# Sheet4.net
KiCad netlist of a schematic drawn in Altium Designer
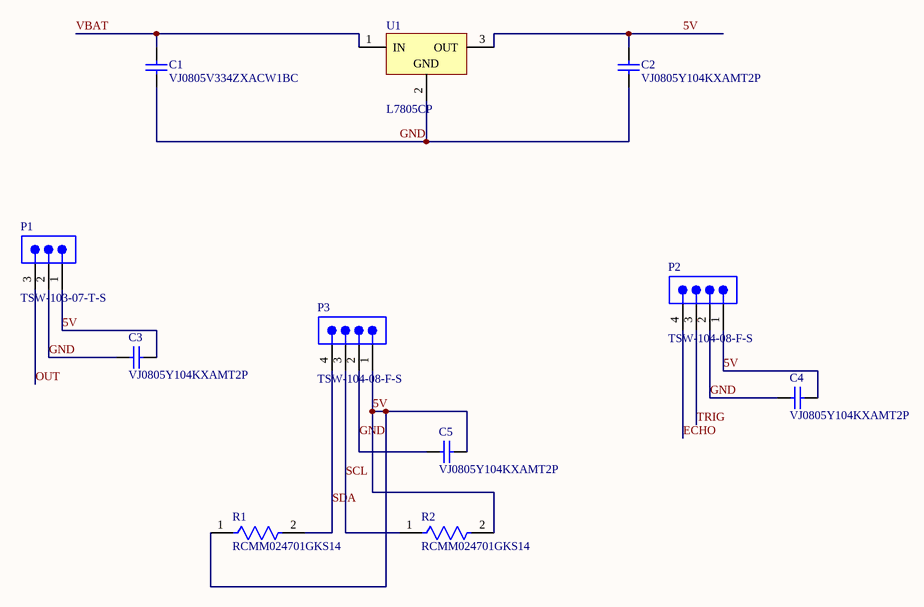
[diagram p0: Sheet4.SchDoc]

(export (version "E")
  (design (tool "Eeschema 10.0.6"))
  (components
    (comp (ref "C1")
      (value "VJ0805V334ZXACW1BC")
      (footprint "CAPC2013X145X50NL20T20")
      (fields (field (name "MANUFACTURER") "Vitramon"))
      (libsource (lib "Altium Content Vault") (part "CAP"))
    )
    (comp (ref "C2")
      (value "VJ0805Y104KXAMT2P")
      (footprint "CAPC2013X145X48LL20T23")
      (fields (field (name "MANUFACTURER") "Vishay"))
      (libsource (lib "Altium Content Vault") (part "CAP"))
    )
    (comp (ref "C3")
      (value "VJ0805Y104KXAMT2P")
      (footprint "CAPC2013X145X48LL20T23")
      (fields (field (name "MANUFACTURER") "Vishay"))
      (libsource (lib "Altium Content Vault") (part "CAP"))
    )
    (comp (ref "C4")
      (value "VJ0805Y104KXAMT2P")
      (footprint "CAPC2013X145X48LL20T23")
      (fields (field (name "MANUFACTURER") "Vishay"))
      (libsource (lib "Altium Content Vault") (part "CAP"))
    )
    (comp (ref "C5")
      (value "VJ0805Y104KXAMT2P")
      (footprint "CAPC2013X145X48LL20T23")
      (fields (field (name "MANUFACTURER") "Vishay"))
      (libsource (lib "Altium Content Vault") (part "CAP"))
    )
    (comp (ref "P1")
      (value "TSW-103-07-T-S")
      (footprint "SMTC-TSW-103-07-X-S")
      (description "0.025\" SQ Post Header, Through-hole, Vertical, -55 to 105 degC, 2.54 mm Pitch, 3-Pin, Male, RoHS")
      (fields (field (name "MANUFACTURER") "Samtec"))
      (libsource (lib "Altium Content Vault") (part "SMTC-TSW-103-X-X-S-X"))
    )
    (comp (ref "P2")
      (value "TSW-104-08-F-S")
      (footprint "SMTC-TSW-104-08-X-S")
      (description "0.025\" SQ Post Header, Through-hole, Vertical, -55 to 125 degC, 2.54 mm Pitch, 4-Pin, Male, RoHS")
      (fields (field (name "MANUFACTURER") "Samtec"))
      (libsource (lib "Altium Content Vault") (part "SMTC-TSW-104-08-X-S"))
    )
    (comp (ref "P3")
      (value "TSW-104-08-F-S")
      (footprint "SMTC-TSW-104-08-X-S")
      (description "0.025\" SQ Post Header, Through-hole, Vertical, -55 to 125 degC, 2.54 mm Pitch, 4-Pin, Male, RoHS")
      (fields (field (name "MANUFACTURER") "Samtec"))
      (libsource (lib "Altium Content Vault") (part "SMTC-TSW-104-08-X-S"))
    )
    (comp (ref "R1")
      (value "RCMM024701GKS14")
      (footprint "FP-RCMM02-MFG")
      (description "RES 4.7K OHM 2% 1/2W AXIAL")
      (fields (field (name "TOLERANCE") "2%"))
      (libsource (lib "Altium Content Vault") (part "1029c3af85768c4190bb7ad29bc67b5"))
    )
    (comp (ref "R2")
      (value "RCMM024701GKS14")
      (footprint "FP-RCMM02-MFG")
      (description "RES 4.7K OHM 2% 1/2W AXIAL")
      (fields (field (name "TOLERANCE") "2%"))
      (libsource (lib "Altium Content Vault") (part "1029c3af85768c4190bb7ad29bc67b5"))
    )
    (comp (ref "U1")
      (value "L7805CP")
      (footprint "TO220FP")
      (description "Positive Voltage Regulator, 5V, 3-Pin TO-220FP")
      (libsource (lib "Altium Content Vault") (part "PM-REG-L4940-SIL3"))
    )
  )
  (nets
    (net (code "1") (name "/5V") (class "Default")
      (node (ref "C2") (pin "2") (pinfunction "2_2") (pintype "passive"))
      (node (ref "C3") (pin "2") (pinfunction "2_2") (pintype "passive"))
      (node (ref "C4") (pin "2") (pinfunction "2_2") (pintype "passive"))
      (node (ref "C5") (pin "2") (pinfunction "2_2") (pintype "passive"))
      (node (ref "P1") (pin "1") (pinfunction "1_1") (pintype "passive"))
      (node (ref "P2") (pin "1") (pinfunction "1_1") (pintype "passive"))
      (node (ref "P3") (pin "1") (pinfunction "1_1") (pintype "passive"))
      (node (ref "R1") (pin "1") (pinfunction "1_1") (pintype "passive"))
      (node (ref "R2") (pin "2") (pinfunction "2_2") (pintype "passive"))
      (node (ref "U1") (pin "3") (pinfunction "OUT_3") (pintype "power_in"))
    )
    (net (code "2") (name "/ECHO") (class "Default")
      (node (ref "P2") (pin "4") (pinfunction "4_4") (pintype "passive"))
    )
    (net (code "3") (name "/GND") (class "Default")
      (node (ref "C1") (pin "1") (pinfunction "1_1") (pintype "passive"))
      (node (ref "C2") (pin "1") (pinfunction "1_1") (pintype "passive"))
      (node (ref "C3") (pin "1") (pinfunction "1_1") (pintype "passive"))
      (node (ref "C4") (pin "1") (pinfunction "1_1") (pintype "passive"))
      (node (ref "C5") (pin "1") (pinfunction "1_1") (pintype "passive"))
      (node (ref "P1") (pin "2") (pinfunction "2_2") (pintype "passive"))
      (node (ref "P2") (pin "2") (pinfunction "2_2") (pintype "passive"))
      (node (ref "P3") (pin "2") (pinfunction "2_2") (pintype "passive"))
      (node (ref "U1") (pin "2") (pinfunction "GND_2") (pintype "power_in"))
    )
    (net (code "4") (name "/OUT") (class "Default")
      (node (ref "P1") (pin "3") (pinfunction "3_3") (pintype "passive"))
    )
    (net (code "5") (name "/SCL") (class "Default")
      (node (ref "P3") (pin "3") (pinfunction "3_3") (pintype "passive"))
      (node (ref "R2") (pin "1") (pinfunction "1_1") (pintype "passive"))
    )
    (net (code "6") (name "/SDA") (class "Default")
      (node (ref "P3") (pin "4") (pinfunction "4_4") (pintype "passive"))
      (node (ref "R1") (pin "2") (pinfunction "2_2") (pintype "passive"))
    )
    (net (code "7") (name "/TRIG") (class "Default")
      (node (ref "P2") (pin "3") (pinfunction "3_3") (pintype "passive"))
    )
    (net (code "8") (name "/VBAT") (class "Default")
      (node (ref "C1") (pin "2") (pinfunction "2_2") (pintype "passive"))
      (node (ref "U1") (pin "1") (pinfunction "IN_1") (pintype "power_in"))
    )
  )
)
